# PLT-01-RevD.net
KiCad netlist of a schematic drawn in EAGLE
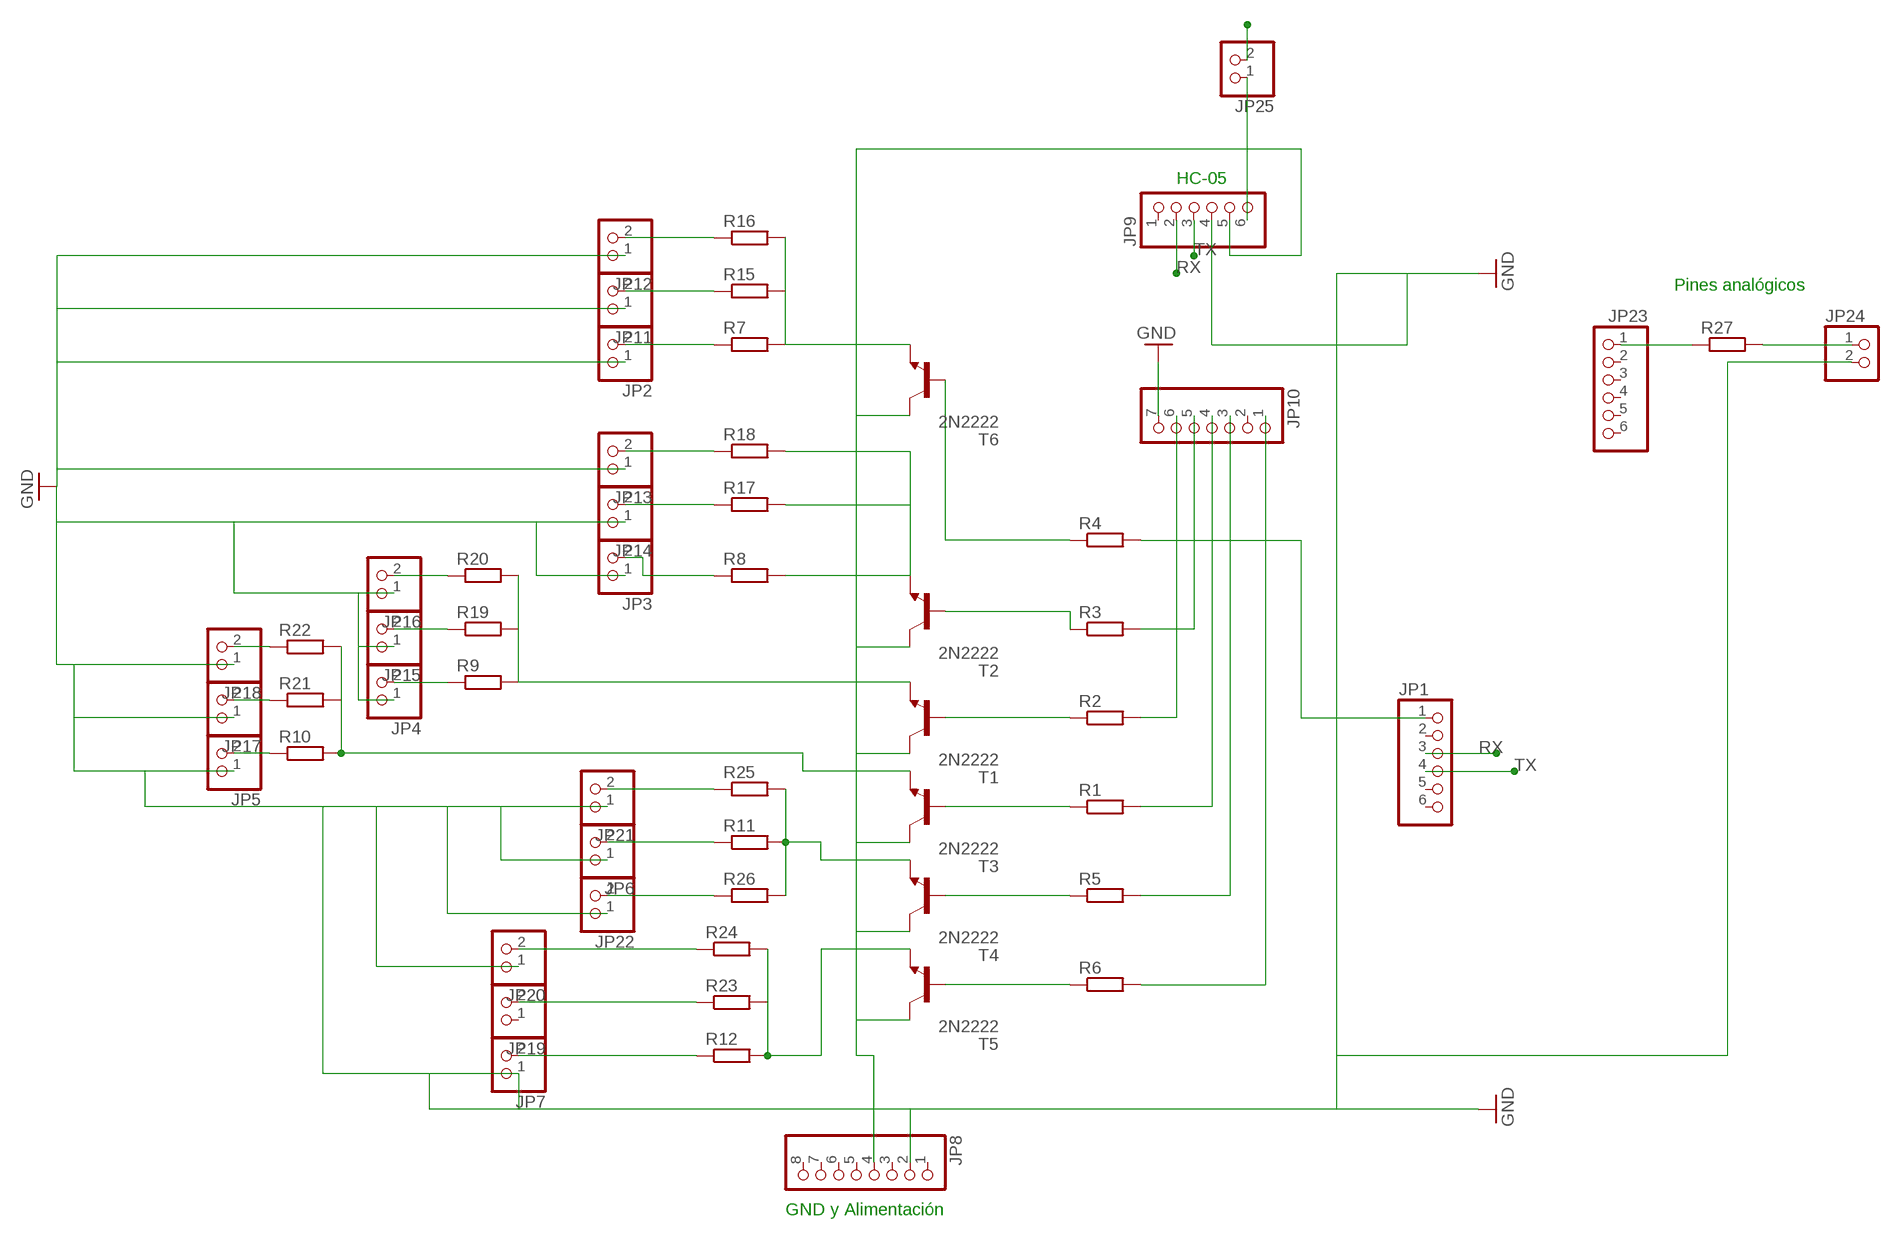
[diagram p0: schematic, sheet 1]

(export (version "E")
  (design (tool "Eeschema 10.0.6"))
  (components
    (comp (ref "JP1")
      (value "PINHD-1X6")
      (footprint "eagle-import:1X06")
      (libsource (lib "eagle-import") (part "PINHD-1X6"))
    )
    (comp (ref "JP2")
      (value "PINHD-1X2")
      (footprint "eagle-import:1X02")
      (libsource (lib "eagle-import") (part "PINHD-1X2"))
    )
    (comp (ref "JP3")
      (value "PINHD-1X2")
      (footprint "eagle-import:1X02")
      (libsource (lib "eagle-import") (part "PINHD-1X2"))
    )
    (comp (ref "JP4")
      (value "PINHD-1X2")
      (footprint "eagle-import:1X02")
      (libsource (lib "eagle-import") (part "PINHD-1X2"))
    )
    (comp (ref "JP5")
      (value "PINHD-1X2")
      (footprint "eagle-import:1X02")
      (libsource (lib "eagle-import") (part "PINHD-1X2"))
    )
    (comp (ref "JP6")
      (value "PINHD-1X2")
      (footprint "eagle-import:1X02")
      (libsource (lib "eagle-import") (part "PINHD-1X2"))
    )
    (comp (ref "JP7")
      (value "PINHD-1X2")
      (footprint "eagle-import:1X02")
      (libsource (lib "eagle-import") (part "PINHD-1X2"))
    )
    (comp (ref "JP8")
      (value "PINHD-1X8")
      (footprint "eagle-import:1X08")
      (libsource (lib "eagle-import") (part "PINHD-1X8"))
    )
    (comp (ref "JP9")
      (value "PINHD-1X6")
      (footprint "eagle-import:1X06")
      (libsource (lib "eagle-import") (part "PINHD-1X6"))
    )
    (comp (ref "JP10")
      (value "PINHD-1X7")
      (footprint "eagle-import:1X07")
      (libsource (lib "eagle-import") (part "PINHD-1X7"))
    )
    (comp (ref "JP11")
      (value "PINHD-1X2")
      (footprint "eagle-import:1X02")
      (libsource (lib "eagle-import") (part "PINHD-1X2"))
    )
    (comp (ref "JP12")
      (value "PINHD-1X2")
      (footprint "eagle-import:1X02")
      (libsource (lib "eagle-import") (part "PINHD-1X2"))
    )
    (comp (ref "JP13")
      (value "PINHD-1X2")
      (footprint "eagle-import:1X02")
      (libsource (lib "eagle-import") (part "PINHD-1X2"))
    )
    (comp (ref "JP14")
      (value "PINHD-1X2")
      (footprint "eagle-import:1X02")
      (libsource (lib "eagle-import") (part "PINHD-1X2"))
    )
    (comp (ref "JP15")
      (value "PINHD-1X2")
      (footprint "eagle-import:1X02")
      (libsource (lib "eagle-import") (part "PINHD-1X2"))
    )
    (comp (ref "JP16")
      (value "PINHD-1X2")
      (footprint "eagle-import:1X02")
      (libsource (lib "eagle-import") (part "PINHD-1X2"))
    )
    (comp (ref "JP17")
      (value "PINHD-1X2")
      (footprint "eagle-import:1X02")
      (libsource (lib "eagle-import") (part "PINHD-1X2"))
    )
    (comp (ref "JP18")
      (value "PINHD-1X2")
      (footprint "eagle-import:1X02")
      (libsource (lib "eagle-import") (part "PINHD-1X2"))
    )
    (comp (ref "JP19")
      (value "PINHD-1X2")
      (footprint "eagle-import:1X02")
      (libsource (lib "eagle-import") (part "PINHD-1X2"))
    )
    (comp (ref "JP20")
      (value "PINHD-1X2")
      (footprint "eagle-import:1X02")
      (libsource (lib "eagle-import") (part "PINHD-1X2"))
    )
    (comp (ref "JP21")
      (value "PINHD-1X2")
      (footprint "eagle-import:1X02")
      (libsource (lib "eagle-import") (part "PINHD-1X2"))
    )
    (comp (ref "JP22")
      (value "PINHD-1X2")
      (footprint "eagle-import:1X02")
      (libsource (lib "eagle-import") (part "PINHD-1X2"))
    )
    (comp (ref "JP23")
      (value "PINHD-1X6")
      (footprint "eagle-import:1X06")
      (libsource (lib "eagle-import") (part "PINHD-1X6"))
    )
    (comp (ref "JP24")
      (value "PINHD-1X2")
      (footprint "eagle-import:1X02")
      (libsource (lib "eagle-import") (part "PINHD-1X2"))
    )
    (comp (ref "JP25")
      (value "PINHD-1X2")
      (footprint "eagle-import:1X02")
      (libsource (lib "eagle-import") (part "PINHD-1X2"))
    )
    (comp (ref "R1")
      (value "R-EU_0207/10")
      (footprint "eagle-import:0207_10")
      (libsource (lib "eagle-import") (part "R-EU_0207/10"))
    )
    (comp (ref "R2")
      (value "R-EU_0207/10")
      (footprint "eagle-import:0207_10")
      (libsource (lib "eagle-import") (part "R-EU_0207/10"))
    )
    (comp (ref "R3")
      (value "R-EU_0207/10")
      (footprint "eagle-import:0207_10")
      (libsource (lib "eagle-import") (part "R-EU_0207/10"))
    )
    (comp (ref "R4")
      (value "R-EU_0207/10")
      (footprint "eagle-import:0207_10")
      (libsource (lib "eagle-import") (part "R-EU_0207/10"))
    )
    (comp (ref "R5")
      (value "R-EU_0207/10")
      (footprint "eagle-import:0207_10")
      (libsource (lib "eagle-import") (part "R-EU_0207/10"))
    )
    (comp (ref "R6")
      (value "R-EU_0207/10")
      (footprint "eagle-import:0207_10")
      (libsource (lib "eagle-import") (part "R-EU_0207/10"))
    )
    (comp (ref "R7")
      (value "R-EU_0207/10")
      (footprint "eagle-import:0207_10")
      (libsource (lib "eagle-import") (part "R-EU_0207/10"))
    )
    (comp (ref "R8")
      (value "R-EU_0207/10")
      (footprint "eagle-import:0207_10")
      (libsource (lib "eagle-import") (part "R-EU_0207/10"))
    )
    (comp (ref "R9")
      (value "R-EU_0207/10")
      (footprint "eagle-import:0207_10")
      (libsource (lib "eagle-import") (part "R-EU_0207/10"))
    )
    (comp (ref "R10")
      (value "R-EU_0207/10")
      (footprint "eagle-import:0207_10")
      (libsource (lib "eagle-import") (part "R-EU_0207/10"))
    )
    (comp (ref "R11")
      (value "R-EU_0207/10")
      (footprint "eagle-import:0207_10")
      (libsource (lib "eagle-import") (part "R-EU_0207/10"))
    )
    (comp (ref "R12")
      (value "R-EU_0207/10")
      (footprint "eagle-import:0207_10")
      (libsource (lib "eagle-import") (part "R-EU_0207/10"))
    )
    (comp (ref "R15")
      (value "R-EU_0207/10")
      (footprint "eagle-import:0207_10")
      (libsource (lib "eagle-import") (part "R-EU_0207/10"))
    )
    (comp (ref "R16")
      (value "R-EU_0207/10")
      (footprint "eagle-import:0207_10")
      (libsource (lib "eagle-import") (part "R-EU_0207/10"))
    )
    (comp (ref "R17")
      (value "R-EU_0207/10")
      (footprint "eagle-import:0207_10")
      (libsource (lib "eagle-import") (part "R-EU_0207/10"))
    )
    (comp (ref "R18")
      (value "R-EU_0207/10")
      (footprint "eagle-import:0207_10")
      (libsource (lib "eagle-import") (part "R-EU_0207/10"))
    )
    (comp (ref "R19")
      (value "R-EU_0207/10")
      (footprint "eagle-import:0207_10")
      (libsource (lib "eagle-import") (part "R-EU_0207/10"))
    )
    (comp (ref "R20")
      (value "R-EU_0207/10")
      (footprint "eagle-import:0207_10")
      (libsource (lib "eagle-import") (part "R-EU_0207/10"))
    )
    (comp (ref "R21")
      (value "R-EU_0207/10")
      (footprint "eagle-import:0207_10")
      (libsource (lib "eagle-import") (part "R-EU_0207/10"))
    )
    (comp (ref "R22")
      (value "R-EU_0207/10")
      (footprint "eagle-import:0207_10")
      (libsource (lib "eagle-import") (part "R-EU_0207/10"))
    )
    (comp (ref "R23")
      (value "R-EU_0207/10")
      (footprint "eagle-import:0207_10")
      (libsource (lib "eagle-import") (part "R-EU_0207/10"))
    )
    (comp (ref "R24")
      (value "R-EU_0207/10")
      (footprint "eagle-import:0207_10")
      (libsource (lib "eagle-import") (part "R-EU_0207/10"))
    )
    (comp (ref "R25")
      (value "R-EU_0207/10")
      (footprint "eagle-import:0207_10")
      (libsource (lib "eagle-import") (part "R-EU_0207/10"))
    )
    (comp (ref "R26")
      (value "R-EU_0207/10")
      (footprint "eagle-import:0207_10")
      (libsource (lib "eagle-import") (part "R-EU_0207/10"))
    )
    (comp (ref "R27")
      (value "R-EU_0207/10")
      (footprint "eagle-import:0207_10")
      (libsource (lib "eagle-import") (part "R-EU_0207/10"))
    )
    (comp (ref "T1")
      (value "2N2222")
      (footprint "eagle-import:TO92-EBC-OVAL")
      (libsource (lib "eagle-import") (part "2N2222"))
    )
    (comp (ref "T2")
      (value "2N2222")
      (footprint "eagle-import:TO92-EBC-OVAL")
      (libsource (lib "eagle-import") (part "2N2222"))
    )
    (comp (ref "T3")
      (value "2N2222")
      (footprint "eagle-import:TO92-EBC-OVAL")
      (libsource (lib "eagle-import") (part "2N2222"))
    )
    (comp (ref "T4")
      (value "2N2222")
      (footprint "eagle-import:TO92-EBC-OVAL")
      (libsource (lib "eagle-import") (part "2N2222"))
    )
    (comp (ref "T5")
      (value "2N2222")
      (footprint "eagle-import:TO92-EBC-OVAL")
      (libsource (lib "eagle-import") (part "2N2222"))
    )
    (comp (ref "T6")
      (value "2N2222")
      (footprint "eagle-import:TO92-EBC-OVAL")
      (libsource (lib "eagle-import") (part "2N2222"))
    )
  )
  (nets
    (net (code "1") (name "/5V") (class "Default")
      (node (ref "JP25") (pin "2") (pinfunction "2_2") (pintype "passive"))
      (node (ref "JP8") (pin "4") (pinfunction "4_4") (pintype "passive"))
      (node (ref "JP9") (pin "5") (pinfunction "5_5") (pintype "passive"))
      (node (ref "T1") (pin "C") (pinfunction "C_C") (pintype "passive"))
      (node (ref "T2") (pin "C") (pinfunction "C_C") (pintype "passive"))
      (node (ref "T3") (pin "C") (pinfunction "C_C") (pintype "passive"))
      (node (ref "T4") (pin "C") (pinfunction "C_C") (pintype "passive"))
      (node (ref "T5") (pin "C") (pinfunction "C_C") (pintype "passive"))
      (node (ref "T6") (pin "C") (pinfunction "C_C") (pintype "passive"))
    )
    (net (code "2") (name "/RX") (class "Default")
      (node (ref "JP1") (pin "3") (pinfunction "3_3") (pintype "passive"))
      (node (ref "JP9") (pin "2") (pinfunction "2_2") (pintype "passive"))
    )
    (net (code "3") (name "/TX") (class "Default")
      (node (ref "JP1") (pin "4") (pinfunction "4_4") (pintype "passive"))
      (node (ref "JP9") (pin "3") (pinfunction "3_3") (pintype "passive"))
    )
    (net (code "4") (name "GND") (class "Default")
      (node (ref "JP10") (pin "7") (pinfunction "7_7") (pintype "passive"))
      (node (ref "JP11") (pin "1") (pinfunction "1_1") (pintype "passive"))
      (node (ref "JP12") (pin "1") (pinfunction "1_1") (pintype "passive"))
      (node (ref "JP13") (pin "1") (pinfunction "1_1") (pintype "passive"))
      (node (ref "JP14") (pin "1") (pinfunction "1_1") (pintype "passive"))
      (node (ref "JP15") (pin "1") (pinfunction "1_1") (pintype "passive"))
      (node (ref "JP16") (pin "1") (pinfunction "1_1") (pintype "passive"))
      (node (ref "JP17") (pin "1") (pinfunction "1_1") (pintype "passive"))
      (node (ref "JP18") (pin "1") (pinfunction "1_1") (pintype "passive"))
      (node (ref "JP2") (pin "1") (pinfunction "1_1") (pintype "passive"))
      (node (ref "JP20") (pin "1") (pinfunction "1_1") (pintype "passive"))
      (node (ref "JP21") (pin "1") (pinfunction "1_1") (pintype "passive"))
      (node (ref "JP22") (pin "1") (pinfunction "1_1") (pintype "passive"))
      (node (ref "JP24") (pin "2") (pinfunction "2_2") (pintype "passive"))
      (node (ref "JP3") (pin "1") (pinfunction "1_1") (pintype "passive"))
      (node (ref "JP4") (pin "1") (pinfunction "1_1") (pintype "passive"))
      (node (ref "JP5") (pin "1") (pinfunction "1_1") (pintype "passive"))
      (node (ref "JP6") (pin "1") (pinfunction "1_1") (pintype "passive"))
      (node (ref "JP7") (pin "1") (pinfunction "1_1") (pintype "passive"))
      (node (ref "JP8") (pin "2") (pinfunction "2_2") (pintype "passive"))
      (node (ref "JP9") (pin "4") (pinfunction "4_4") (pintype "passive"))
    )
    (net (code "5") (name "Net-(JP1-Pad1)") (class "Default")
      (node (ref "JP1") (pin "1") (pinfunction "1_1") (pintype "passive"))
      (node (ref "R4") (pin "2") (pinfunction "2_2") (pintype "passive"))
    )
    (net (code "6") (name "Net-(JP2-Pad2)") (class "Default")
      (node (ref "JP2") (pin "2") (pinfunction "2_2") (pintype "passive"))
      (node (ref "R7") (pin "1") (pinfunction "1_1") (pintype "passive"))
    )
    (net (code "7") (name "Net-(JP3-Pad2)") (class "Default")
      (node (ref "JP3") (pin "2") (pinfunction "2_2") (pintype "passive"))
      (node (ref "R8") (pin "1") (pinfunction "1_1") (pintype "passive"))
    )
    (net (code "8") (name "Net-(JP4-Pad2)") (class "Default")
      (node (ref "JP4") (pin "2") (pinfunction "2_2") (pintype "passive"))
      (node (ref "R9") (pin "1") (pinfunction "1_1") (pintype "passive"))
    )
    (net (code "9") (name "Net-(JP5-Pad2)") (class "Default")
      (node (ref "JP5") (pin "2") (pinfunction "2_2") (pintype "passive"))
      (node (ref "R10") (pin "1") (pinfunction "1_1") (pintype "passive"))
    )
    (net (code "10") (name "Net-(JP6-Pad2)") (class "Default")
      (node (ref "JP6") (pin "2") (pinfunction "2_2") (pintype "passive"))
      (node (ref "R11") (pin "1") (pinfunction "1_1") (pintype "passive"))
    )
    (net (code "11") (name "Net-(JP7-Pad2)") (class "Default")
      (node (ref "JP7") (pin "2") (pinfunction "2_2") (pintype "passive"))
      (node (ref "R12") (pin "1") (pinfunction "1_1") (pintype "passive"))
    )
    (net (code "12") (name "Net-(JP10-Pad1)") (class "Default")
      (node (ref "JP10") (pin "1") (pinfunction "1_1") (pintype "passive"))
      (node (ref "R6") (pin "2") (pinfunction "2_2") (pintype "passive"))
    )
    (net (code "13") (name "Net-(JP10-Pad3)") (class "Default")
      (node (ref "JP10") (pin "3") (pinfunction "3_3") (pintype "passive"))
      (node (ref "R5") (pin "2") (pinfunction "2_2") (pintype "passive"))
    )
    (net (code "14") (name "Net-(JP10-Pad4)") (class "Default")
      (node (ref "JP10") (pin "4") (pinfunction "4_4") (pintype "passive"))
      (node (ref "R1") (pin "2") (pinfunction "2_2") (pintype "passive"))
    )
    (net (code "15") (name "Net-(JP10-Pad5)") (class "Default")
      (node (ref "JP10") (pin "5") (pinfunction "5_5") (pintype "passive"))
      (node (ref "R3") (pin "2") (pinfunction "2_2") (pintype "passive"))
    )
    (net (code "16") (name "Net-(JP10-Pad6)") (class "Default")
      (node (ref "JP10") (pin "6") (pinfunction "6_6") (pintype "passive"))
      (node (ref "R2") (pin "2") (pinfunction "2_2") (pintype "passive"))
    )
    (net (code "17") (name "Net-(JP11-Pad2)") (class "Default")
      (node (ref "JP11") (pin "2") (pinfunction "2_2") (pintype "passive"))
      (node (ref "R15") (pin "1") (pinfunction "1_1") (pintype "passive"))
    )
    (net (code "18") (name "Net-(JP12-Pad2)") (class "Default")
      (node (ref "JP12") (pin "2") (pinfunction "2_2") (pintype "passive"))
      (node (ref "R16") (pin "1") (pinfunction "1_1") (pintype "passive"))
    )
    (net (code "19") (name "Net-(JP13-Pad2)") (class "Default")
      (node (ref "JP13") (pin "2") (pinfunction "2_2") (pintype "passive"))
      (node (ref "R18") (pin "1") (pinfunction "1_1") (pintype "passive"))
    )
    (net (code "20") (name "Net-(JP14-Pad2)") (class "Default")
      (node (ref "JP14") (pin "2") (pinfunction "2_2") (pintype "passive"))
      (node (ref "R17") (pin "1") (pinfunction "1_1") (pintype "passive"))
    )
    (net (code "21") (name "Net-(JP15-Pad2)") (class "Default")
      (node (ref "JP15") (pin "2") (pinfunction "2_2") (pintype "passive"))
      (node (ref "R19") (pin "1") (pinfunction "1_1") (pintype "passive"))
    )
    (net (code "22") (name "Net-(JP16-Pad2)") (class "Default")
      (node (ref "JP16") (pin "2") (pinfunction "2_2") (pintype "passive"))
      (node (ref "R20") (pin "1") (pinfunction "1_1") (pintype "passive"))
    )
    (net (code "23") (name "Net-(JP17-Pad2)") (class "Default")
      (node (ref "JP17") (pin "2") (pinfunction "2_2") (pintype "passive"))
      (node (ref "R21") (pin "1") (pinfunction "1_1") (pintype "passive"))
    )
    (net (code "24") (name "Net-(JP18-Pad2)") (class "Default")
      (node (ref "JP18") (pin "2") (pinfunction "2_2") (pintype "passive"))
      (node (ref "R22") (pin "1") (pinfunction "1_1") (pintype "passive"))
    )
    (net (code "25") (name "Net-(JP19-Pad2)") (class "Default")
      (node (ref "JP19") (pin "2") (pinfunction "2_2") (pintype "passive"))
      (node (ref "R23") (pin "1") (pinfunction "1_1") (pintype "passive"))
    )
    (net (code "26") (name "Net-(JP20-Pad2)") (class "Default")
      (node (ref "JP20") (pin "2") (pinfunction "2_2") (pintype "passive"))
      (node (ref "R24") (pin "1") (pinfunction "1_1") (pintype "passive"))
    )
    (net (code "27") (name "Net-(JP21-Pad2)") (class "Default")
      (node (ref "JP21") (pin "2") (pinfunction "2_2") (pintype "passive"))
      (node (ref "R25") (pin "1") (pinfunction "1_1") (pintype "passive"))
    )
    (net (code "28") (name "Net-(JP22-Pad2)") (class "Default")
      (node (ref "JP22") (pin "2") (pinfunction "2_2") (pintype "passive"))
      (node (ref "R26") (pin "1") (pinfunction "1_1") (pintype "passive"))
    )
    (net (code "29") (name "Net-(JP23-Pad1)") (class "Default")
      (node (ref "JP23") (pin "1") (pinfunction "1_1") (pintype "passive"))
      (node (ref "R27") (pin "1") (pinfunction "1_1") (pintype "passive"))
    )
    (net (code "30") (name "Net-(JP24-Pad1)") (class "Default")
      (node (ref "JP24") (pin "1") (pinfunction "1_1") (pintype "passive"))
      (node (ref "R27") (pin "2") (pinfunction "2_2") (pintype "passive"))
    )
    (net (code "31") (name "Net-(JP25-Pad1)") (class "Default")
      (node (ref "JP25") (pin "1") (pinfunction "1_1") (pintype "passive"))
      (node (ref "JP9") (pin "6") (pinfunction "6_6") (pintype "passive"))
    )
    (net (code "32") (name "Net-(R1-Pad1)") (class "Default")
      (node (ref "R1") (pin "1") (pinfunction "1_1") (pintype "passive"))
      (node (ref "T3") (pin "B") (pinfunction "B_B") (pintype "passive"))
    )
    (net (code "33") (name "Net-(R2-Pad1)") (class "Default")
      (node (ref "R2") (pin "1") (pinfunction "1_1") (pintype "passive"))
      (node (ref "T1") (pin "B") (pinfunction "B_B") (pintype "passive"))
    )
    (net (code "34") (name "Net-(R3-Pad1)") (class "Default")
      (node (ref "R3") (pin "1") (pinfunction "1_1") (pintype "passive"))
      (node (ref "T2") (pin "B") (pinfunction "B_B") (pintype "passive"))
    )
    (net (code "35") (name "Net-(R4-Pad1)") (class "Default")
      (node (ref "R4") (pin "1") (pinfunction "1_1") (pintype "passive"))
      (node (ref "T6") (pin "B") (pinfunction "B_B") (pintype "passive"))
    )
    (net (code "36") (name "Net-(R5-Pad1)") (class "Default")
      (node (ref "R5") (pin "1") (pinfunction "1_1") (pintype "passive"))
      (node (ref "T4") (pin "B") (pinfunction "B_B") (pintype "passive"))
    )
    (net (code "37") (name "Net-(R6-Pad1)") (class "Default")
      (node (ref "R6") (pin "1") (pinfunction "1_1") (pintype "passive"))
      (node (ref "T5") (pin "B") (pinfunction "B_B") (pintype "passive"))
    )
    (net (code "38") (name "Net-(R10-Pad2)") (class "Default")
      (node (ref "R10") (pin "2") (pinfunction "2_2") (pintype "passive"))
      (node (ref "R21") (pin "2") (pinfunction "2_2") (pintype "passive"))
      (node (ref "R22") (pin "2") (pinfunction "2_2") (pintype "passive"))
      (node (ref "T3") (pin "E") (pinfunction "E_E") (pintype "passive"))
    )
    (net (code "39") (name "Net-(R11-Pad2)") (class "Default")
      (node (ref "R11") (pin "2") (pinfunction "2_2") (pintype "passive"))
      (node (ref "R25") (pin "2") (pinfunction "2_2") (pintype "passive"))
      (node (ref "R26") (pin "2") (pinfunction "2_2") (pintype "passive"))
      (node (ref "T4") (pin "E") (pinfunction "E_E") (pintype "passive"))
    )
    (net (code "40") (name "Net-(R12-Pad2)") (class "Default")
      (node (ref "R12") (pin "2") (pinfunction "2_2") (pintype "passive"))
      (node (ref "R23") (pin "2") (pinfunction "2_2") (pintype "passive"))
      (node (ref "R24") (pin "2") (pinfunction "2_2") (pintype "passive"))
      (node (ref "T5") (pin "E") (pinfunction "E_E") (pintype "passive"))
    )
    (net (code "41") (name "Net-(R15-Pad2)") (class "Default")
      (node (ref "R15") (pin "2") (pinfunction "2_2") (pintype "passive"))
      (node (ref "R16") (pin "2") (pinfunction "2_2") (pintype "passive"))
      (node (ref "R7") (pin "2") (pinfunction "2_2") (pintype "passive"))
      (node (ref "T6") (pin "E") (pinfunction "E_E") (pintype "passive"))
    )
    (net (code "42") (name "Net-(R17-Pad2)") (class "Default")
      (node (ref "R17") (pin "2") (pinfunction "2_2") (pintype "passive"))
      (node (ref "R18") (pin "2") (pinfunction "2_2") (pintype "passive"))
      (node (ref "R8") (pin "2") (pinfunction "2_2") (pintype "passive"))
      (node (ref "T2") (pin "E") (pinfunction "E_E") (pintype "passive"))
    )
    (net (code "43") (name "Net-(R19-Pad2)") (class "Default")
      (node (ref "R19") (pin "2") (pinfunction "2_2") (pintype "passive"))
      (node (ref "R20") (pin "2") (pinfunction "2_2") (pintype "passive"))
      (node (ref "R9") (pin "2") (pinfunction "2_2") (pintype "passive"))
      (node (ref "T1") (pin "E") (pinfunction "E_E") (pintype "passive"))
    )
    (net (code "44") (name "unconnected-(JP1-Pad2)") (class "Default")
      (node (ref "JP1") (pin "2") (pinfunction "2_2") (pintype "passive"))
    )
    (net (code "45") (name "unconnected-(JP1-Pad5)") (class "Default")
      (node (ref "JP1") (pin "5") (pinfunction "5_5") (pintype "passive"))
    )
    (net (code "46") (name "unconnected-(JP1-Pad6)") (class "Default")
      (node (ref "JP1") (pin "6") (pinfunction "6_6") (pintype "passive"))
    )
    (net (code "47") (name "unconnected-(JP8-Pad1)") (class "Default")
      (node (ref "JP8") (pin "1") (pinfunction "1_1") (pintype "passive"))
    )
    (net (code "48") (name "unconnected-(JP8-Pad3)") (class "Default")
      (node (ref "JP8") (pin "3") (pinfunction "3_3") (pintype "passive"))
    )
    (net (code "49") (name "unconnected-(JP8-Pad5)") (class "Default")
      (node (ref "JP8") (pin "5") (pinfunction "5_5") (pintype "passive"))
    )
    (net (code "50") (name "unconnected-(JP8-Pad6)") (class "Default")
      (node (ref "JP8") (pin "6") (pinfunction "6_6") (pintype "passive"))
    )
    (net (code "51") (name "unconnected-(JP8-Pad7)") (class "Default")
      (node (ref "JP8") (pin "7") (pinfunction "7_7") (pintype "passive"))
    )
    (net (code "52") (name "unconnected-(JP8-Pad8)") (class "Default")
      (node (ref "JP8") (pin "8") (pinfunction "8_8") (pintype "passive"))
    )
    (net (code "53") (name "unconnected-(JP9-Pad1)") (class "Default")
      (node (ref "JP9") (pin "1") (pinfunction "1_1") (pintype "passive"))
    )
    (net (code "54") (name "unconnected-(JP10-Pad2)") (class "Default")
      (node (ref "JP10") (pin "2") (pinfunction "2_2") (pintype "passive"))
    )
    (net (code "55") (name "unconnected-(JP19-Pad1)") (class "Default")
      (node (ref "JP19") (pin "1") (pinfunction "1_1") (pintype "passive"))
    )
    (net (code "56") (name "unconnected-(JP23-Pad2)") (class "Default")
      (node (ref "JP23") (pin "2") (pinfunction "2_2") (pintype "passive"))
    )
    (net (code "57") (name "unconnected-(JP23-Pad3)") (class "Default")
      (node (ref "JP23") (pin "3") (pinfunction "3_3") (pintype "passive"))
    )
    (net (code "58") (name "unconnected-(JP23-Pad4)") (class "Default")
      (node (ref "JP23") (pin "4") (pinfunction "4_4") (pintype "passive"))
    )
    (net (code "59") (name "unconnected-(JP23-Pad5)") (class "Default")
      (node (ref "JP23") (pin "5") (pinfunction "5_5") (pintype "passive"))
    )
    (net (code "60") (name "unconnected-(JP23-Pad6)") (class "Default")
      (node (ref "JP23") (pin "6") (pinfunction "6_6") (pintype "passive"))
    )
  )
)
